# Fonte.net
KiCad netlist of a schematic drawn in Altium Designer
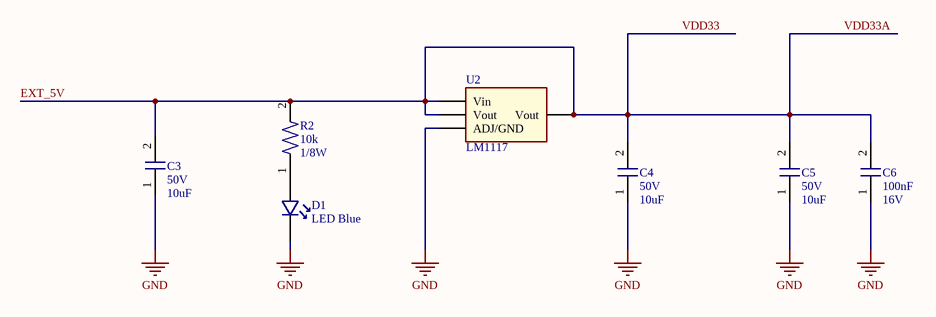
[diagram p0: Fonte.SchDoc]

(export (version "E")
  (design (tool "Eeschema 10.0.6"))
  (components
    (comp (ref "C3")
      (value "CAP 10uF/50V")
      (footprint "CAP 10uF/50V")
      (description "10uF ±1% 50V Ceramic Capacitor C0G, NP0 0805 (2012 Metric)")
      (fields (field (name "VOLTAGE") "50V") (field (name "CAPACITANCE") "10uF"))
      (libsource (lib "Ceramic Capacitors 0805 50V") (part "CAP  10uF/50V"))
    )
    (comp (ref "C4")
      (value "CAP 10uF/50V")
      (footprint "CAP 10uF/50V")
      (description "10uF ±1% 50V Ceramic Capacitor C0G, NP0 0805 (2012 Metric)")
      (fields (field (name "VOLTAGE") "50V") (field (name "CAPACITANCE") "10uF"))
      (libsource (lib "Ceramic Capacitors 0805 50V") (part "CAP  10uF/50V"))
    )
    (comp (ref "C5")
      (value "CAP 10uF/50V")
      (footprint "CAP 10uF/50V")
      (description "10uF ±1% 50V Ceramic Capacitor C0G, NP0 0805 (2012 Metric)")
      (fields (field (name "VOLTAGE") "50V") (field (name "CAPACITANCE") "10uF"))
      (libsource (lib "Ceramic Capacitors 0805 50V") (part "CAP  10uF/50V"))
    )
    (comp (ref "C6")
      (value "CAP 100nF/16V")
      (footprint "CAP 100nF/16V")
      (description "0.1µF ±20% 16V Ceramic Capacitor Y5V (F) 0805 (2012 Metric)")
      (fields (field (name "CAPACITANCE") "100nF") (field (name "VOLTAGE") "16V"))
      (libsource (lib "Ceramic Capacitors 0805 16V") (part "CAP 100nF/16V"))
    )
    (comp (ref "D1")
      (value "LED Blue")
      (footprint "LED Blue")
      (description "Blue 470nm LED Indication - Discrete 3.3V 0805 (2012 Metric)")
      (libsource (lib "LEDs") (part "LED Blue"))
    )
    (comp (ref "R2")
      (value "RES 0603")
      (footprint "RES 10k 1% 1/8W")
      (fields (field (name "RESISTENCE") "10k") (field (name "POWER") "1/8W"))
      (libsource (lib "Resistors 0603") (part "RES 10k 1% 1/8W"))
    )
    (comp (ref "U2")
      (value "LM1117")
      (footprint "LM1117")
      (description "Linear Voltage Regulator IC Positive Fixed 1 Output 3.3V 1A SOT-223")
      (libsource (lib "ICs - Voltage Regulators") (part "LM1117"))
    )
  )
  (nets
    (net (code "1") (name "/EXT_5V") (class "Default")
      (node (ref "C3") (pin "2") (pinfunction "2_2") (pintype "passive"))
      (node (ref "C4") (pin "2") (pinfunction "2_2") (pintype "passive"))
      (node (ref "C5") (pin "2") (pinfunction "2_2") (pintype "passive"))
      (node (ref "C6") (pin "2") (pinfunction "2_2") (pintype "passive"))
      (node (ref "R2") (pin "2") (pinfunction "2_2") (pintype "passive"))
      (node (ref "U2") (pin "2") (pinfunction "Vout_2") (pintype "power_in"))
      (node (ref "U2") (pin "3") (pinfunction "Vin_3") (pintype "power_in"))
      (node (ref "U2") (pin "4") (pinfunction "Vout_4") (pintype "power_in"))
    )
    (net (code "2") (name "GND") (class "Default")
      (node (ref "C3") (pin "1") (pinfunction "1_1") (pintype "passive"))
      (node (ref "C4") (pin "1") (pinfunction "1_1") (pintype "passive"))
      (node (ref "C5") (pin "1") (pinfunction "1_1") (pintype "passive"))
      (node (ref "C6") (pin "1") (pinfunction "1_1") (pintype "passive"))
      (node (ref "D1") (pin "K") (pinfunction "K_K") (pintype "passive"))
      (node (ref "U2") (pin "1") (pinfunction "ADJ/GND_1") (pintype "power_in"))
    )
    (net (code "3") (name "Net-(D1-PadA)") (class "Default")
      (node (ref "D1") (pin "A") (pinfunction "A_A") (pintype "passive"))
      (node (ref "R2") (pin "1") (pinfunction "1_1") (pintype "passive"))
    )
  )
)
